# Leddriverboard.net
KiCad netlist of a schematic drawn in EAGLE
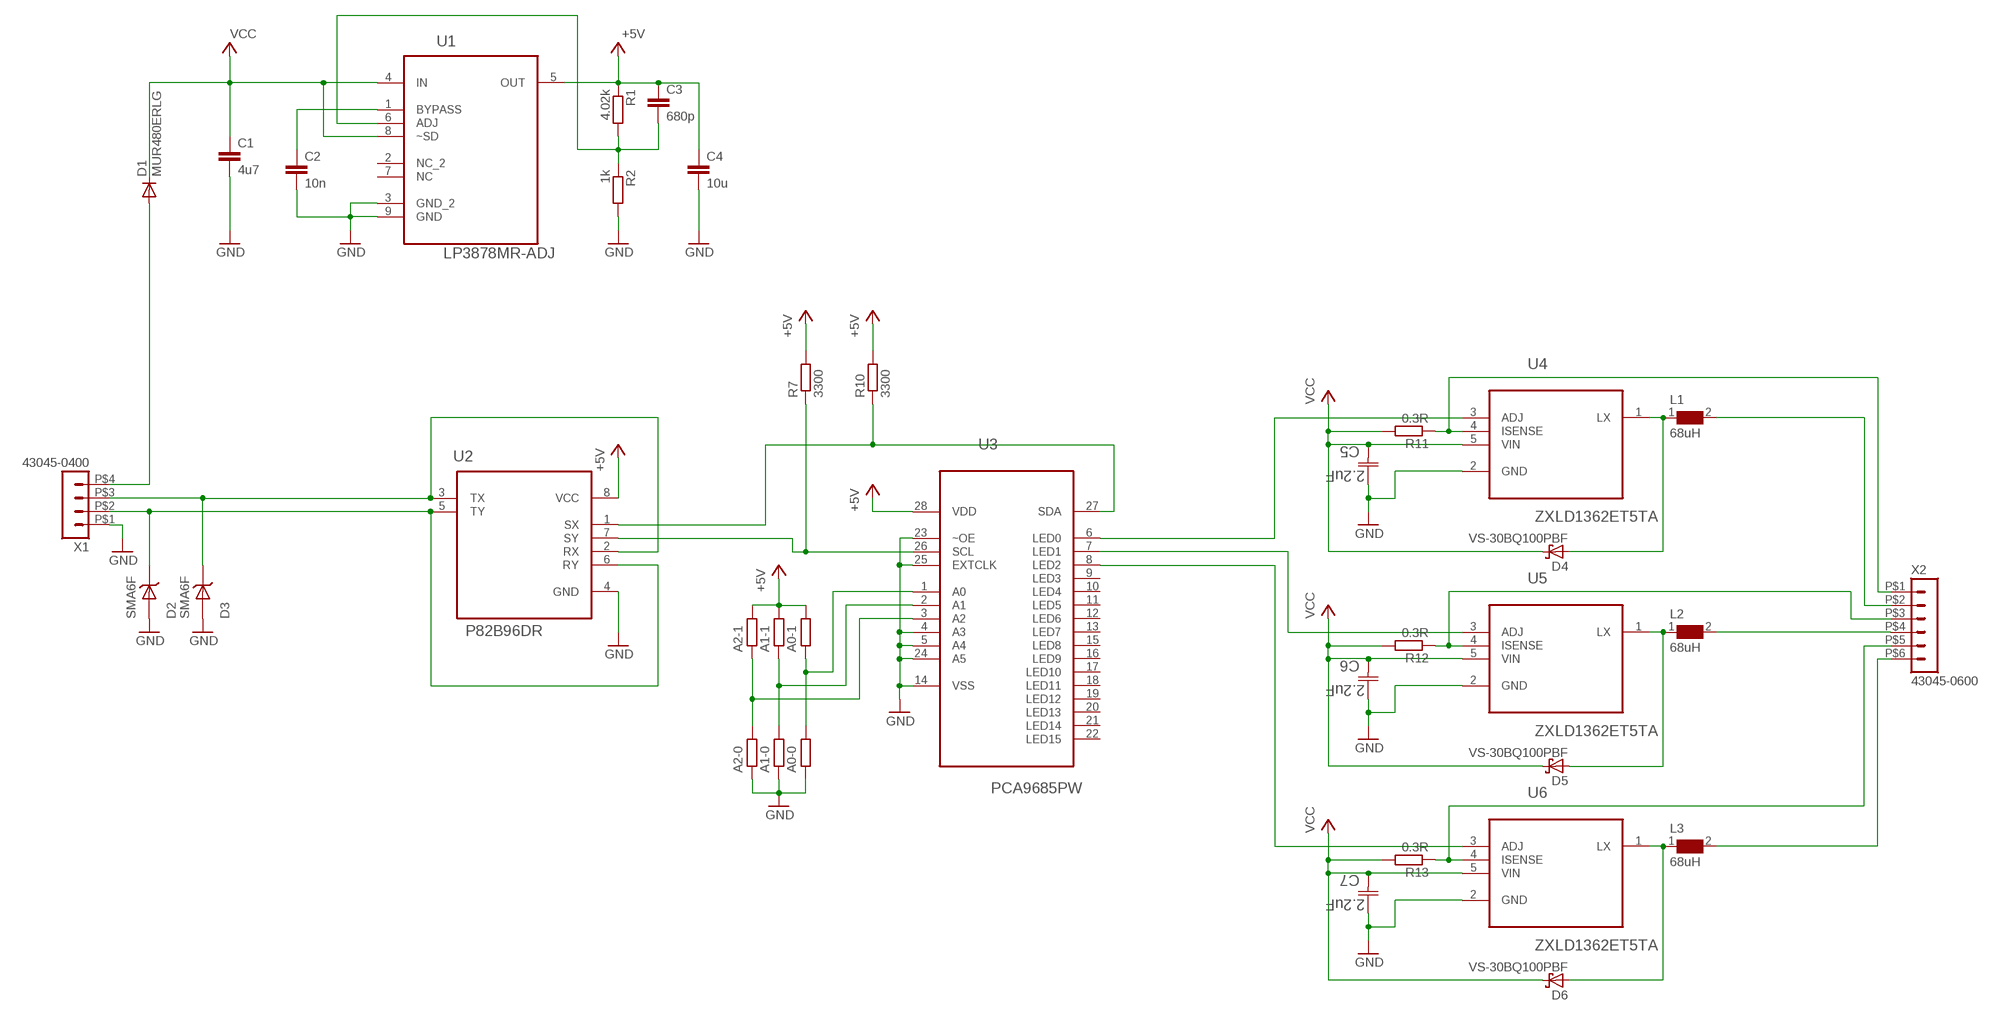
[diagram p0: schematic, sheet 1]

(export (version "E")
  (design (tool "Eeschema 10.0.6"))
  (components
    (comp (ref "C1")
      (value "4u7")
      (footprint "eagle-import:C1206")
      (libsource (lib "eagle-import") (part "C-EUC1206"))
    )
    (comp (ref "C2")
      (value "10n")
      (footprint "eagle-import:C1608")
      (libsource (lib "eagle-import") (part "C-EUC1608"))
    )
    (comp (ref "C3")
      (value "680p")
      (footprint "eagle-import:C1608")
      (libsource (lib "eagle-import") (part "C-EUC1608"))
    )
    (comp (ref "C4")
      (value "10u")
      (footprint "eagle-import:C2012")
      (libsource (lib "eagle-import") (part "C-EUC2012"))
    )
    (comp (ref "C5")
      (value "2.2uF")
      (footprint "eagle-import:CAPC2013X152N")
      (fields (field (name "MPN") "08053C225KAT2A") (field (name "TOLERANCE") "±10%"))
      (libsource (lib "eagle-import") (part "08053C225KAT2A"))
    )
    (comp (ref "C6")
      (value "2.2uF")
      (footprint "eagle-import:CAPC2013X152N")
      (fields (field (name "MPN") "08053C225KAT2A") (field (name "TOLERANCE") "±10%"))
      (libsource (lib "eagle-import") (part "08053C225KAT2A"))
    )
    (comp (ref "C7")
      (value "2.2uF")
      (footprint "eagle-import:CAPC2013X152N")
      (fields (field (name "MPN") "08053C225KAT2A") (field (name "TOLERANCE") "±10%"))
      (libsource (lib "eagle-import") (part "08053C225KAT2A"))
    )
    (comp (ref "D1")
      (value "MUR480ERLG")
      (footprint "eagle-import:DO41-10")
      (libsource (lib "eagle-import") (part "MUR150RL"))
    )
    (comp (ref "D2")
      (value "SMA6F")
      (footprint "eagle-import:DO-221AC")
      (libsource (lib "eagle-import") (part "SMA6F"))
    )
    (comp (ref "D3")
      (value "SMA6F")
      (footprint "eagle-import:DO-221AC")
      (libsource (lib "eagle-import") (part "SMA6F"))
    )
    (comp (ref "D4")
      (value "VS-30BQ100PBF")
      (footprint "eagle-import:DO-214AB")
      (libsource (lib "eagle-import") (part "VS-30BQ100PBF"))
    )
    (comp (ref "D5")
      (value "VS-30BQ100PBF")
      (footprint "eagle-import:DO-214AB")
      (libsource (lib "eagle-import") (part "VS-30BQ100PBF"))
    )
    (comp (ref "D6")
      (value "VS-30BQ100PBF")
      (footprint "eagle-import:DO-214AB")
      (libsource (lib "eagle-import") (part "VS-30BQ100PBF"))
    )
    (comp (ref "L1")
      (value "68uH")
      (footprint "eagle-import:L")
      (fields (field (name "MPN") "74456168"))
      (libsource (lib "eagle-import") (part "WE-PD4_L-74456168"))
    )
    (comp (ref "L2")
      (value "68uH")
      (footprint "eagle-import:L")
      (fields (field (name "MPN") "74456168"))
      (libsource (lib "eagle-import") (part "WE-PD4_L-74456168"))
    )
    (comp (ref "L3")
      (value "68uH")
      (footprint "eagle-import:L")
      (fields (field (name "MPN") "74456168"))
      (libsource (lib "eagle-import") (part "WE-PD4_L-74456168"))
    )
    (comp (ref "R1")
      (value "4.02k")
      (footprint "eagle-import:R0603")
      (libsource (lib "eagle-import") (part "resistor_R-EU_R0603"))
    )
    (comp (ref "R2")
      (value "1k")
      (footprint "eagle-import:R0603")
      (libsource (lib "eagle-import") (part "resistor_R-EU_R0603"))
    )
    (comp (ref "R3")
      (value "A2-1")
      (footprint "eagle-import:R0402")
      (libsource (lib "eagle-import") (part "resistor_R-EU_R0402"))
    )
    (comp (ref "R4")
      (value "A2-0")
      (footprint "eagle-import:R0402")
      (libsource (lib "eagle-import") (part "resistor_R-EU_R0402"))
    )
    (comp (ref "R5")
      (value "A1-1")
      (footprint "eagle-import:R0402")
      (libsource (lib "eagle-import") (part "resistor_R-EU_R0402"))
    )
    (comp (ref "R6")
      (value "A1-0")
      (footprint "eagle-import:R0402")
      (libsource (lib "eagle-import") (part "resistor_R-EU_R0402"))
    )
    (comp (ref "R7")
      (value "3300")
      (footprint "eagle-import:0204_7")
      (libsource (lib "eagle-import") (part "R-EU_0204/7"))
    )
    (comp (ref "R8")
      (value "A0-1")
      (footprint "eagle-import:R0402")
      (libsource (lib "eagle-import") (part "resistor_R-EU_R0402"))
    )
    (comp (ref "R9")
      (value "A0-0")
      (footprint "eagle-import:R0402")
      (libsource (lib "eagle-import") (part "resistor_R-EU_R0402"))
    )
    (comp (ref "R10")
      (value "3300")
      (footprint "eagle-import:0204_7")
      (libsource (lib "eagle-import") (part "R-EU_0204/7"))
    )
    (comp (ref "R11")
      (value "0.3R")
      (footprint "eagle-import:R0603")
      (libsource (lib "eagle-import") (part "resistor_R-EU_R0603"))
    )
    (comp (ref "R12")
      (value "0.3R")
      (footprint "eagle-import:R0603")
      (libsource (lib "eagle-import") (part "resistor_R-EU_R0603"))
    )
    (comp (ref "R13")
      (value "0.3R")
      (footprint "eagle-import:R0603")
      (libsource (lib "eagle-import") (part "resistor_R-EU_R0603"))
    )
    (comp (ref "U1")
      (value "LP3878MR-ADJ")
      (footprint "eagle-import:SOIC127P600X168-8N")
      (libsource (lib "eagle-import") (part "LP3878MR-ADJ"))
    )
    (comp (ref "U2")
      (value "P82B96DR")
      (footprint "eagle-import:SOIC127P600X175-8N")
      (libsource (lib "eagle-import") (part "P82B96DR"))
    )
    (comp (ref "U3")
      (value "PCA9685PW")
      (footprint "eagle-import:SOP65P640X110-28N")
      (libsource (lib "eagle-import") (part "PCA9685PW"))
    )
    (comp (ref "U4")
      (value "ZXLD1362ET5TA")
      (footprint "eagle-import:SOT95P270X145-5N")
      (libsource (lib "eagle-import") (part "ZXLD1362ET5TA"))
    )
    (comp (ref "U5")
      (value "ZXLD1362ET5TA")
      (footprint "eagle-import:SOT95P270X145-5N")
      (libsource (lib "eagle-import") (part "ZXLD1362ET5TA"))
    )
    (comp (ref "U6")
      (value "ZXLD1362ET5TA")
      (footprint "eagle-import:SOT95P270X145-5N")
      (libsource (lib "eagle-import") (part "ZXLD1362ET5TA"))
    )
    (comp (ref "X1")
      (value "43045-0400")
      (footprint "eagle-import:43045-0400")
      (libsource (lib "eagle-import") (part "HEADER_POS4_?43045-0401"))
    )
    (comp (ref "X2")
      (value "43045-0600")
      (footprint "eagle-import:43045-0600")
      (libsource (lib "eagle-import") (part "HEADER_POS6_?43045-0600"))
    )
  )
  (nets
    (net (code "1") (name "+5V") (class "Default")
      (node (ref "C3") (pin "1") (pinfunction "1_1") (pintype "passive"))
      (node (ref "C4") (pin "1") (pinfunction "1_1") (pintype "passive"))
      (node (ref "R1") (pin "1") (pinfunction "1_1") (pintype "passive"))
      (node (ref "R10") (pin "2") (pinfunction "2_2") (pintype "passive"))
      (node (ref "R3") (pin "2") (pinfunction "2_2") (pintype "passive"))
      (node (ref "R5") (pin "2") (pinfunction "2_2") (pintype "passive"))
      (node (ref "R7") (pin "2") (pinfunction "2_2") (pintype "passive"))
      (node (ref "R8") (pin "2") (pinfunction "2_2") (pintype "passive"))
      (node (ref "U1") (pin "5") (pinfunction "OUT_5") (pintype "output"))
      (node (ref "U2") (pin "8") (pinfunction "VCC_8") (pintype "power_in"))
      (node (ref "U3") (pin "28") (pinfunction "VDD_28") (pintype "power_in"))
    )
    (net (code "2") (name "GND") (class "Default")
      (node (ref "C1") (pin "2") (pinfunction "2_2") (pintype "passive"))
      (node (ref "C2") (pin "2") (pinfunction "2_2") (pintype "passive"))
      (node (ref "C4") (pin "2") (pinfunction "2_2") (pintype "passive"))
      (node (ref "C5") (pin "1") (pinfunction "C1_1") (pintype "passive"))
      (node (ref "C6") (pin "1") (pinfunction "C1_1") (pintype "passive"))
      (node (ref "C7") (pin "1") (pinfunction "C1_1") (pintype "passive"))
      (node (ref "D2") (pin "AN") (pinfunction "AN_AN") (pintype "bidirectional"))
      (node (ref "D3") (pin "AN") (pinfunction "AN_AN") (pintype "bidirectional"))
      (node (ref "R2") (pin "2") (pinfunction "2_2") (pintype "passive"))
      (node (ref "R4") (pin "1") (pinfunction "1_1") (pintype "passive"))
      (node (ref "R6") (pin "1") (pinfunction "1_1") (pintype "passive"))
      (node (ref "R9") (pin "1") (pinfunction "1_1") (pintype "passive"))
      (node (ref "U1") (pin "3") (pinfunction "GND_2_3") (pintype "passive"))
      (node (ref "U1") (pin "9") (pinfunction "GND_9") (pintype "passive"))
      (node (ref "U2") (pin "4") (pinfunction "GND_4") (pintype "passive"))
      (node (ref "U3") (pin "14") (pinfunction "VSS_14") (pintype "passive"))
      (node (ref "U3") (pin "23") (pinfunction "~{OE}_23") (pintype "input"))
      (node (ref "U3") (pin "24") (pinfunction "A5_24") (pintype "input"))
      (node (ref "U3") (pin "25") (pinfunction "EXTCLK_25") (pintype "input"))
      (node (ref "U3") (pin "4") (pinfunction "A3_4") (pintype "input"))
      (node (ref "U3") (pin "5") (pinfunction "A4_5") (pintype "input"))
      (node (ref "U4") (pin "2") (pinfunction "GND_2") (pintype "passive"))
      (node (ref "U5") (pin "2") (pinfunction "GND_2") (pintype "passive"))
      (node (ref "U6") (pin "2") (pinfunction "GND_2") (pintype "passive"))
      (node (ref "X1") (pin "P$1") (pinfunction "1_P$1") (pintype "passive"))
    )
    (net (code "3") (name "Net-(U1-ADJ)") (class "Default")
      (node (ref "C3") (pin "2") (pinfunction "2_2") (pintype "passive"))
      (node (ref "R1") (pin "2") (pinfunction "2_2") (pintype "passive"))
      (node (ref "R2") (pin "1") (pinfunction "1_1") (pintype "passive"))
      (node (ref "U1") (pin "6") (pinfunction "ADJ_6") (pintype "passive"))
    )
    (net (code "4") (name "Net-(U1-BYPASS)") (class "Default")
      (node (ref "C2") (pin "1") (pinfunction "1_1") (pintype "passive"))
      (node (ref "U1") (pin "1") (pinfunction "BYPASS_1") (pintype "passive"))
    )
    (net (code "5") (name "Net-(U2-RX)") (class "Default")
      (node (ref "D3") (pin "KAT") (pinfunction "KAT_KAT") (pintype "bidirectional"))
      (node (ref "U2") (pin "2") (pinfunction "RX_2") (pintype "input"))
      (node (ref "U2") (pin "3") (pinfunction "TX_3") (pintype "output"))
      (node (ref "X1") (pin "P$3") (pinfunction "3_P$3") (pintype "passive"))
    )
    (net (code "6") (name "Net-(U2-RY)") (class "Default")
      (node (ref "D2") (pin "KAT") (pinfunction "KAT_KAT") (pintype "bidirectional"))
      (node (ref "U2") (pin "5") (pinfunction "TY_5") (pintype "output"))
      (node (ref "U2") (pin "6") (pinfunction "RY_6") (pintype "input"))
      (node (ref "X1") (pin "P$2") (pinfunction "2_P$2") (pintype "passive"))
    )
    (net (code "7") (name "Net-(U2-SX)") (class "Default")
      (node (ref "R10") (pin "1") (pinfunction "1_1") (pintype "passive"))
      (node (ref "U2") (pin "1") (pinfunction "SX_1") (pintype "input"))
      (node (ref "U3") (pin "27") (pinfunction "SDA_27") (pintype "bidirectional"))
    )
    (net (code "8") (name "Net-(U2-SY)") (class "Default")
      (node (ref "R7") (pin "1") (pinfunction "1_1") (pintype "passive"))
      (node (ref "U2") (pin "7") (pinfunction "SY_7") (pintype "input"))
      (node (ref "U3") (pin "26") (pinfunction "SCL_26") (pintype "input"))
    )
    (net (code "9") (name "Net-(U3-A0)") (class "Default")
      (node (ref "R8") (pin "1") (pinfunction "1_1") (pintype "passive"))
      (node (ref "R9") (pin "2") (pinfunction "2_2") (pintype "passive"))
      (node (ref "U3") (pin "1") (pinfunction "A0_1") (pintype "input"))
    )
    (net (code "10") (name "Net-(U3-A1)") (class "Default")
      (node (ref "R5") (pin "1") (pinfunction "1_1") (pintype "passive"))
      (node (ref "R6") (pin "2") (pinfunction "2_2") (pintype "passive"))
      (node (ref "U3") (pin "2") (pinfunction "A1_2") (pintype "input"))
    )
    (net (code "11") (name "Net-(U3-A2)") (class "Default")
      (node (ref "R3") (pin "1") (pinfunction "1_1") (pintype "passive"))
      (node (ref "R4") (pin "2") (pinfunction "2_2") (pintype "passive"))
      (node (ref "U3") (pin "3") (pinfunction "A2_3") (pintype "input"))
    )
    (net (code "12") (name "Net-(U3-LED0)") (class "Default")
      (node (ref "U3") (pin "6") (pinfunction "LED0_6") (pintype "output"))
      (node (ref "U4") (pin "3") (pinfunction "ADJ_3") (pintype "input"))
    )
    (net (code "13") (name "Net-(U3-LED1)") (class "Default")
      (node (ref "U3") (pin "7") (pinfunction "LED1_7") (pintype "output"))
      (node (ref "U5") (pin "3") (pinfunction "ADJ_3") (pintype "input"))
    )
    (net (code "14") (name "Net-(U3-LED2)") (class "Default")
      (node (ref "U3") (pin "8") (pinfunction "LED2_8") (pintype "output"))
      (node (ref "U6") (pin "3") (pinfunction "ADJ_3") (pintype "input"))
    )
    (net (code "15") (name "Net-(U4-ISENSE)") (class "Default")
      (node (ref "R11") (pin "1") (pinfunction "1_1") (pintype "passive"))
      (node (ref "U4") (pin "4") (pinfunction "ISENSE_4") (pintype "input"))
      (node (ref "X2") (pin "P$1") (pinfunction "1_P$1") (pintype "passive"))
    )
    (net (code "16") (name "Net-(U4-LX)") (class "Default")
      (node (ref "D4") (pin "A") (pinfunction "A_A") (pintype "passive"))
      (node (ref "L1") (pin "1") (pinfunction "1_1") (pintype "passive"))
      (node (ref "U4") (pin "1") (pinfunction "LX_1") (pintype "output"))
    )
    (net (code "17") (name "Net-(U5-ISENSE)") (class "Default")
      (node (ref "R12") (pin "1") (pinfunction "1_1") (pintype "passive"))
      (node (ref "U5") (pin "4") (pinfunction "ISENSE_4") (pintype "input"))
      (node (ref "X2") (pin "P$3") (pinfunction "3_P$3") (pintype "passive"))
    )
    (net (code "18") (name "Net-(U5-LX)") (class "Default")
      (node (ref "D5") (pin "A") (pinfunction "A_A") (pintype "passive"))
      (node (ref "L2") (pin "1") (pinfunction "1_1") (pintype "passive"))
      (node (ref "U5") (pin "1") (pinfunction "LX_1") (pintype "output"))
    )
    (net (code "19") (name "Net-(U6-ISENSE)") (class "Default")
      (node (ref "R13") (pin "1") (pinfunction "1_1") (pintype "passive"))
      (node (ref "U6") (pin "4") (pinfunction "ISENSE_4") (pintype "input"))
      (node (ref "X2") (pin "P$5") (pinfunction "5_P$5") (pintype "passive"))
    )
    (net (code "20") (name "Net-(U6-LX)") (class "Default")
      (node (ref "D6") (pin "A") (pinfunction "A_A") (pintype "passive"))
      (node (ref "L3") (pin "1") (pinfunction "1_1") (pintype "passive"))
      (node (ref "U6") (pin "1") (pinfunction "LX_1") (pintype "output"))
    )
    (net (code "21") (name "Net-(X1-4)") (class "Default")
      (node (ref "D1") (pin "A") (pinfunction "A_A") (pintype "passive"))
      (node (ref "X1") (pin "P$4") (pinfunction "4_P$4") (pintype "passive"))
    )
    (net (code "22") (name "Net-(X2-2)") (class "Default")
      (node (ref "L1") (pin "2") (pinfunction "2_2") (pintype "passive"))
      (node (ref "X2") (pin "P$2") (pinfunction "2_P$2") (pintype "passive"))
    )
    (net (code "23") (name "Net-(X2-4)") (class "Default")
      (node (ref "L2") (pin "2") (pinfunction "2_2") (pintype "passive"))
      (node (ref "X2") (pin "P$4") (pinfunction "4_P$4") (pintype "passive"))
    )
    (net (code "24") (name "Net-(X2-6)") (class "Default")
      (node (ref "L3") (pin "2") (pinfunction "2_2") (pintype "passive"))
      (node (ref "X2") (pin "P$6") (pinfunction "6_P$6") (pintype "passive"))
    )
    (net (code "25") (name "VCC") (class "Default")
      (node (ref "C1") (pin "1") (pinfunction "1_1") (pintype "passive"))
      (node (ref "C5") (pin "2") (pinfunction "C2_2") (pintype "passive"))
      (node (ref "C6") (pin "2") (pinfunction "C2_2") (pintype "passive"))
      (node (ref "C7") (pin "2") (pinfunction "C2_2") (pintype "passive"))
      (node (ref "D1") (pin "C") (pinfunction "C_C") (pintype "passive"))
      (node (ref "D4") (pin "K") (pinfunction "C_K") (pintype "passive"))
      (node (ref "D5") (pin "K") (pinfunction "C_K") (pintype "passive"))
      (node (ref "D6") (pin "K") (pinfunction "C_K") (pintype "passive"))
      (node (ref "R11") (pin "2") (pinfunction "2_2") (pintype "passive"))
      (node (ref "R12") (pin "2") (pinfunction "2_2") (pintype "passive"))
      (node (ref "R13") (pin "2") (pinfunction "2_2") (pintype "passive"))
      (node (ref "U1") (pin "4") (pinfunction "IN_4") (pintype "input"))
      (node (ref "U1") (pin "8") (pinfunction "~{SD}_8") (pintype "passive"))
      (node (ref "U4") (pin "5") (pinfunction "VIN_5") (pintype "input"))
      (node (ref "U5") (pin "5") (pinfunction "VIN_5") (pintype "input"))
      (node (ref "U6") (pin "5") (pinfunction "VIN_5") (pintype "input"))
    )
    (net (code "26") (name "unconnected-(U1-NC-Pad7)") (class "Default")
      (node (ref "U1") (pin "7") (pinfunction "NC_7") (pintype "no_connect"))
    )
    (net (code "27") (name "unconnected-(U1-NC_2-Pad2)") (class "Default")
      (node (ref "U1") (pin "2") (pinfunction "NC_2_2") (pintype "no_connect"))
    )
    (net (code "28") (name "unconnected-(U3-LED3-Pad9)") (class "Default")
      (node (ref "U3") (pin "9") (pinfunction "LED3_9") (pintype "output"))
    )
    (net (code "29") (name "unconnected-(U3-LED4-Pad10)") (class "Default")
      (node (ref "U3") (pin "10") (pinfunction "LED4_10") (pintype "output"))
    )
    (net (code "30") (name "unconnected-(U3-LED5-Pad11)") (class "Default")
      (node (ref "U3") (pin "11") (pinfunction "LED5_11") (pintype "output"))
    )
    (net (code "31") (name "unconnected-(U3-LED6-Pad12)") (class "Default")
      (node (ref "U3") (pin "12") (pinfunction "LED6_12") (pintype "output"))
    )
    (net (code "32") (name "unconnected-(U3-LED7-Pad13)") (class "Default")
      (node (ref "U3") (pin "13") (pinfunction "LED7_13") (pintype "output"))
    )
    (net (code "33") (name "unconnected-(U3-LED8-Pad15)") (class "Default")
      (node (ref "U3") (pin "15") (pinfunction "LED8_15") (pintype "output"))
    )
    (net (code "34") (name "unconnected-(U3-LED9-Pad16)") (class "Default")
      (node (ref "U3") (pin "16") (pinfunction "LED9_16") (pintype "output"))
    )
    (net (code "35") (name "unconnected-(U3-LED10-Pad17)") (class "Default")
      (node (ref "U3") (pin "17") (pinfunction "LED10_17") (pintype "output"))
    )
    (net (code "36") (name "unconnected-(U3-LED11-Pad18)") (class "Default")
      (node (ref "U3") (pin "18") (pinfunction "LED11_18") (pintype "output"))
    )
    (net (code "37") (name "unconnected-(U3-LED12-Pad19)") (class "Default")
      (node (ref "U3") (pin "19") (pinfunction "LED12_19") (pintype "output"))
    )
    (net (code "38") (name "unconnected-(U3-LED13-Pad20)") (class "Default")
      (node (ref "U3") (pin "20") (pinfunction "LED13_20") (pintype "output"))
    )
    (net (code "39") (name "unconnected-(U3-LED14-Pad21)") (class "Default")
      (node (ref "U3") (pin "21") (pinfunction "LED14_21") (pintype "output"))
    )
    (net (code "40") (name "unconnected-(U3-LED15-Pad22)") (class "Default")
      (node (ref "U3") (pin "22") (pinfunction "LED15_22") (pintype "output"))
    )
  )
)
